# ConverterModule12V18A.net
KiCad netlist of a schematic drawn in Altium Designer
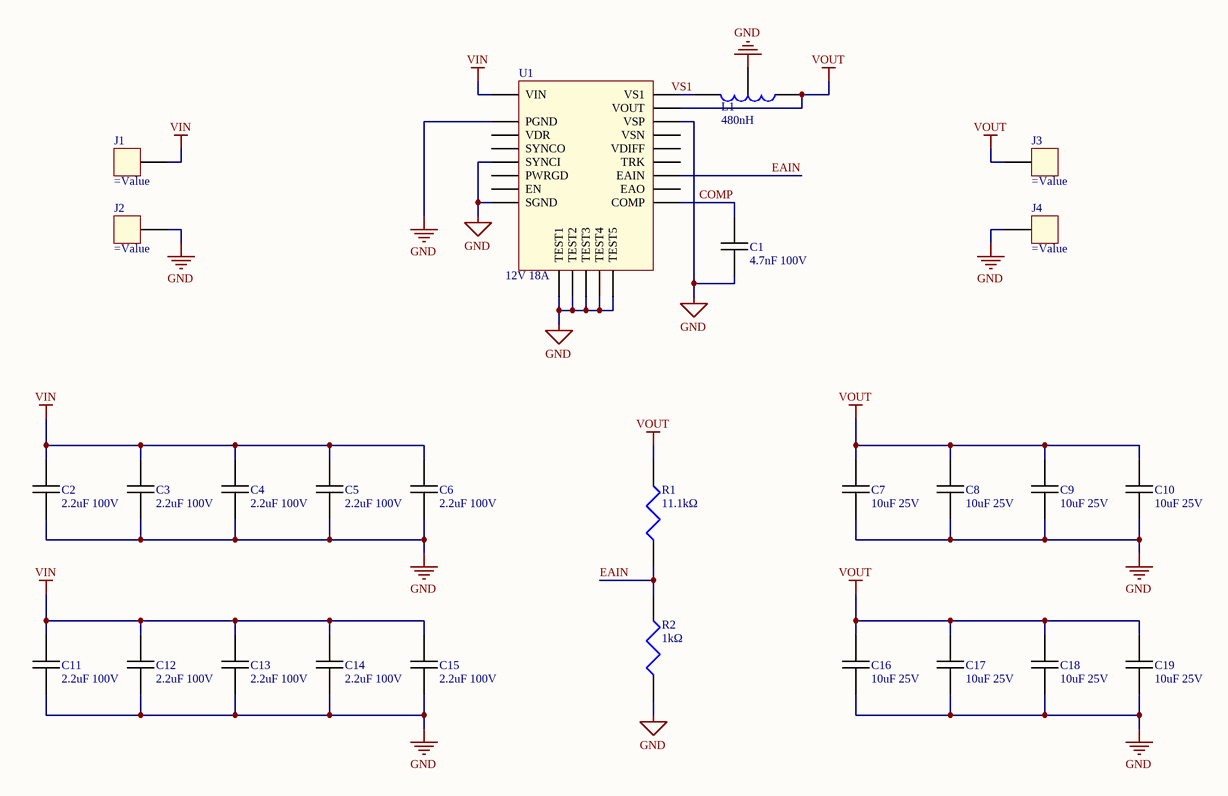
[diagram p0: ConverterModule12V18A.SchDoc]

(export (version "E")
  (design (tool "Eeschema 10.0.6"))
  (components
    (comp (ref "C1")
      (value "4.7nF 100V")
      (footprint "C1608 Generic")
      (description "TDK CAP CER 4700PF 100V C0G 0603")
      (fields
        (field (name "PART NUMBER") "C1608C0G2A472J080AC")
        (field (name "MANUFACTURER") "TDK Corporation")
      )
      (libsource (lib "MinesROV") (part "C1608C0G2A472J080AC"))
    )
    (comp (ref "C2")
      (value "2.2uF 100V")
      (footprint "HMK325B7225MM-P")
      (description "Taiyo Yuden CAP CER 2.2UF 100V X7R 1210")
      (fields (field (name "PART NUMBER") "HMK325B7225MM-P") (field (name "MANUFACTURER") "Taiyo Yuden"))
      (libsource (lib "MinesROV") (part "HMK325B7225MM-P"))
    )
    (comp (ref "C3")
      (value "2.2uF 100V")
      (footprint "HMK325B7225MM-P")
      (description "Taiyo Yuden CAP CER 2.2UF 100V X7R 1210")
      (fields (field (name "PART NUMBER") "HMK325B7225MM-P") (field (name "MANUFACTURER") "Taiyo Yuden"))
      (libsource (lib "MinesROV") (part "HMK325B7225MM-P"))
    )
    (comp (ref "C4")
      (value "2.2uF 100V")
      (footprint "HMK325B7225MM-P")
      (description "Taiyo Yuden CAP CER 2.2UF 100V X7R 1210")
      (fields (field (name "PART NUMBER") "HMK325B7225MM-P") (field (name "MANUFACTURER") "Taiyo Yuden"))
      (libsource (lib "MinesROV") (part "HMK325B7225MM-P"))
    )
    (comp (ref "C5")
      (value "2.2uF 100V")
      (footprint "HMK325B7225MM-P")
      (description "Taiyo Yuden CAP CER 2.2UF 100V X7R 1210")
      (fields (field (name "PART NUMBER") "HMK325B7225MM-P") (field (name "MANUFACTURER") "Taiyo Yuden"))
      (libsource (lib "MinesROV") (part "HMK325B7225MM-P"))
    )
    (comp (ref "C6")
      (value "2.2uF 100V")
      (footprint "HMK325B7225MM-P")
      (description "Taiyo Yuden CAP CER 2.2UF 100V X7R 1210")
      (fields (field (name "PART NUMBER") "HMK325B7225MM-P") (field (name "MANUFACTURER") "Taiyo Yuden"))
      (libsource (lib "MinesROV") (part "HMK325B7225MM-P"))
    )
    (comp (ref "C7")
      (value "10uF 25V")
      (footprint "C1210C106M3RACTU")
      (description "KEMET CAP CER 10UF 25V X7R 1210")
      (fields (field (name "PART NUMBER") "C1210C106M3RACTU") (field (name "MANUFACTURER") "KEMET"))
      (libsource (lib "MinesROV") (part "C1210C106M3RACTU"))
    )
    (comp (ref "C8")
      (value "10uF 25V")
      (footprint "C1210C106M3RACTU")
      (description "KEMET CAP CER 10UF 25V X7R 1210")
      (fields (field (name "PART NUMBER") "C1210C106M3RACTU") (field (name "MANUFACTURER") "KEMET"))
      (libsource (lib "MinesROV") (part "C1210C106M3RACTU"))
    )
    (comp (ref "C9")
      (value "10uF 25V")
      (footprint "C1210C106M3RACTU")
      (description "KEMET CAP CER 10UF 25V X7R 1210")
      (fields (field (name "PART NUMBER") "C1210C106M3RACTU") (field (name "MANUFACTURER") "KEMET"))
      (libsource (lib "MinesROV") (part "C1210C106M3RACTU"))
    )
    (comp (ref "C10")
      (value "10uF 25V")
      (footprint "C1210C106M3RACTU")
      (description "KEMET CAP CER 10UF 25V X7R 1210")
      (fields (field (name "PART NUMBER") "C1210C106M3RACTU") (field (name "MANUFACTURER") "KEMET"))
      (libsource (lib "MinesROV") (part "C1210C106M3RACTU"))
    )
    (comp (ref "C11")
      (value "2.2uF 100V")
      (footprint "HMK325B7225MM-P")
      (description "Taiyo Yuden CAP CER 2.2UF 100V X7R 1210")
      (fields (field (name "PART NUMBER") "HMK325B7225MM-P") (field (name "MANUFACTURER") "Taiyo Yuden"))
      (libsource (lib "MinesROV") (part "HMK325B7225MM-P"))
    )
    (comp (ref "C12")
      (value "2.2uF 100V")
      (footprint "HMK325B7225MM-P")
      (description "Taiyo Yuden CAP CER 2.2UF 100V X7R 1210")
      (fields (field (name "PART NUMBER") "HMK325B7225MM-P") (field (name "MANUFACTURER") "Taiyo Yuden"))
      (libsource (lib "MinesROV") (part "HMK325B7225MM-P"))
    )
    (comp (ref "C13")
      (value "2.2uF 100V")
      (footprint "HMK325B7225MM-P")
      (description "Taiyo Yuden CAP CER 2.2UF 100V X7R 1210")
      (fields (field (name "PART NUMBER") "HMK325B7225MM-P") (field (name "MANUFACTURER") "Taiyo Yuden"))
      (libsource (lib "MinesROV") (part "HMK325B7225MM-P"))
    )
    (comp (ref "C14")
      (value "2.2uF 100V")
      (footprint "HMK325B7225MM-P")
      (description "Taiyo Yuden CAP CER 2.2UF 100V X7R 1210")
      (fields (field (name "PART NUMBER") "HMK325B7225MM-P") (field (name "MANUFACTURER") "Taiyo Yuden"))
      (libsource (lib "MinesROV") (part "HMK325B7225MM-P"))
    )
    (comp (ref "C15")
      (value "2.2uF 100V")
      (footprint "HMK325B7225MM-P")
      (description "Taiyo Yuden CAP CER 2.2UF 100V X7R 1210")
      (fields (field (name "PART NUMBER") "HMK325B7225MM-P") (field (name "MANUFACTURER") "Taiyo Yuden"))
      (libsource (lib "MinesROV") (part "HMK325B7225MM-P"))
    )
    (comp (ref "C16")
      (value "10uF 25V")
      (footprint "C1210C106M3RACTU")
      (description "KEMET CAP CER 10UF 25V X7R 1210")
      (fields (field (name "PART NUMBER") "C1210C106M3RACTU") (field (name "MANUFACTURER") "KEMET"))
      (libsource (lib "MinesROV") (part "C1210C106M3RACTU"))
    )
    (comp (ref "C17")
      (value "10uF 25V")
      (footprint "C1210C106M3RACTU")
      (description "KEMET CAP CER 10UF 25V X7R 1210")
      (fields (field (name "PART NUMBER") "C1210C106M3RACTU") (field (name "MANUFACTURER") "KEMET"))
      (libsource (lib "MinesROV") (part "C1210C106M3RACTU"))
    )
    (comp (ref "C18")
      (value "10uF 25V")
      (footprint "C1210C106M3RACTU")
      (description "KEMET CAP CER 10UF 25V X7R 1210")
      (fields (field (name "PART NUMBER") "C1210C106M3RACTU") (field (name "MANUFACTURER") "KEMET"))
      (libsource (lib "MinesROV") (part "C1210C106M3RACTU"))
    )
    (comp (ref "C19")
      (value "10uF 25V")
      (footprint "C1210C106M3RACTU")
      (description "KEMET CAP CER 10UF 25V X7R 1210")
      (fields (field (name "PART NUMBER") "C1210C106M3RACTU") (field (name "MANUFACTURER") "KEMET"))
      (libsource (lib "MinesROV") (part "C1210C106M3RACTU"))
    )
    (comp (ref "J1")
      (value "~")
      (footprint "M3-Bolt-Down")
      (description "Generic bolt-down mount w/exposed copper pad")
      (libsource (lib "") (part "M3-Bolt-Down_1"))
    )
    (comp (ref "J2")
      (value "~")
      (footprint "M3-Bolt-Down")
      (description "Generic bolt-down mount w/exposed copper pad")
      (libsource (lib "") (part "M3-Bolt-Down_1"))
    )
    (comp (ref "J3")
      (value "~")
      (footprint "M3-Bolt-Down")
      (description "Generic bolt-down mount w/exposed copper pad")
      (libsource (lib "MinesROV") (part "M3-Bolt-Down"))
    )
    (comp (ref "J4")
      (value "~")
      (footprint "M3-Bolt-Down")
      (description "Generic bolt-down mount w/exposed copper pad")
      (libsource (lib "MinesROV") (part "M3-Bolt-Down"))
    )
    (comp (ref "L1")
      (value "480nH")
      (footprint "PA5120.481NLT")
      (description "Pulse FIXED IND 480NH 32A 1.7MOHM SMD")
      (fields
        (field (name "MANUFACTURER") "Pulse Electronics Power")
        (field (name "PART NUMBER") "PA5120.481NLT")
      )
      (libsource (lib "MinesROV") (part "PA5120.481NLT"))
    )
    (comp (ref "R1")
      (value "11.1kΩ")
      (footprint "RNCF0603 Generic")
      (description "Stackpole RES 11.1K OHM 0.1% 1/10W 0603")
      (fields
        (field (name "PART NUMBER") "RNCF0603BTE11K1")
        (field (name "MANUFACTURER") "Stackpole Electronics Inc")
      )
      (libsource (lib "MinesROV") (part "RNCF0603BTE11K1"))
    )
    (comp (ref "R2")
      (value "1kΩ")
      (footprint "RNCF0603 Generic")
      (description "Stackpole RES 1K OHM 0.01% 1/10W 0603")
      (fields
        (field (name "PART NUMBER") "RNCF0603TKY1K00")
        (field (name "MANUFACTURER") "Stackpole Electronics Inc")
      )
      (libsource (lib "MinesROV") (part "RNCF0603TKY1K00"))
    )
    (comp (ref "U1")
      (value "12V 18A")
      (footprint "PI3526-00-LGIZ")
      (description "Vicor DC DC CONVERTER 12V 18A")
      (fields (field (name "MANUFACTURER") "Vicor Corporation") (field (name "PART NUMBER") "PI3526-00-LGIZ"))
      (libsource (lib "MinesROV") (part "PI3526-00-LGIZ"))
    )
  )
  (nets
    (net (code "1") (name "/COMP") (class "Default")
      (node (ref "C1") (pin "1") (pinfunction "1_1") (pintype "passive"))
      (node (ref "U1") (pin "B1") (pinfunction "COMP_B1") (pintype "passive"))
    )
    (net (code "2") (name "/EAIN") (class "Default")
      (node (ref "R1") (pin "2") (pinfunction "2_2") (pintype "passive"))
      (node (ref "R2") (pin "2") (pinfunction "2_2") (pintype "passive"))
      (node (ref "U1") (pin "A2") (pinfunction "EAIN_A2") (pintype "passive"))
    )
    (net (code "3") (name "/VS1") (class "Default")
      (node (ref "L1") (pin "2") (pinfunction "2_2") (pintype "passive"))
      (node (ref "U1") (pin "BLOCK1") (pinfunction "VS1_BLOCK1") (pintype "passive"))
    )
    (net (code "4") (name "GND") (class "Default")
      (node (ref "C1") (pin "2") (pinfunction "2_2") (pintype "passive"))
      (node (ref "C10") (pin "1") (pinfunction "1_1") (pintype "passive"))
      (node (ref "C11") (pin "2") (pinfunction "2_2") (pintype "passive"))
      (node (ref "C12") (pin "2") (pinfunction "2_2") (pintype "passive"))
      (node (ref "C13") (pin "2") (pinfunction "2_2") (pintype "passive"))
      (node (ref "C14") (pin "2") (pinfunction "2_2") (pintype "passive"))
      (node (ref "C15") (pin "2") (pinfunction "2_2") (pintype "passive"))
      (node (ref "C16") (pin "1") (pinfunction "1_1") (pintype "passive"))
      (node (ref "C17") (pin "1") (pinfunction "1_1") (pintype "passive"))
      (node (ref "C18") (pin "1") (pinfunction "1_1") (pintype "passive"))
      (node (ref "C19") (pin "1") (pinfunction "1_1") (pintype "passive"))
      (node (ref "C2") (pin "2") (pinfunction "2_2") (pintype "passive"))
      (node (ref "C3") (pin "2") (pinfunction "2_2") (pintype "passive"))
      (node (ref "C4") (pin "2") (pinfunction "2_2") (pintype "passive"))
      (node (ref "C5") (pin "2") (pinfunction "2_2") (pintype "passive"))
      (node (ref "C6") (pin "2") (pinfunction "2_2") (pintype "passive"))
      (node (ref "C7") (pin "1") (pinfunction "1_1") (pintype "passive"))
      (node (ref "C8") (pin "1") (pinfunction "1_1") (pintype "passive"))
      (node (ref "C9") (pin "1") (pinfunction "1_1") (pintype "passive"))
      (node (ref "J2") (pin "1") (pinfunction "1_1") (pintype "passive"))
      (node (ref "J4") (pin "1") (pinfunction "1_1") (pintype "passive"))
      (node (ref "L1") (pin "3") (pinfunction "3_3") (pintype "passive"))
      (node (ref "R2") (pin "1") (pinfunction "1_1") (pintype "passive"))
      (node (ref "U1") (pin "A5") (pinfunction "VSP_A5") (pintype "passive"))
      (node (ref "U1") (pin "BLOCK2") (pinfunction "PGND_BLOCK2") (pintype "passive"))
      (node (ref "U1") (pin "BLOCK5") (pinfunction "SGND_BLOCK5") (pintype "passive"))
      (node (ref "U1") (pin "E1") (pinfunction "TEST5_E1") (pintype "passive"))
      (node (ref "U1") (pin "H1") (pinfunction "TEST4_H1") (pintype "passive"))
      (node (ref "U1") (pin "J1") (pinfunction "TEST3_J1") (pintype "passive"))
      (node (ref "U1") (pin "K1") (pinfunction "TEST2_K1") (pintype "passive"))
      (node (ref "U1") (pin "K2") (pinfunction "TEST1_K2") (pintype "passive"))
      (node (ref "U1") (pin "K4") (pinfunction "SYNCI_K4") (pintype "passive"))
    )
    (net (code "5") (name "VIN") (class "Default")
      (node (ref "C11") (pin "1") (pinfunction "1_1") (pintype "passive"))
      (node (ref "C12") (pin "1") (pinfunction "1_1") (pintype "passive"))
      (node (ref "C13") (pin "1") (pinfunction "1_1") (pintype "passive"))
      (node (ref "C14") (pin "1") (pinfunction "1_1") (pintype "passive"))
      (node (ref "C15") (pin "1") (pinfunction "1_1") (pintype "passive"))
      (node (ref "C2") (pin "1") (pinfunction "1_1") (pintype "passive"))
      (node (ref "C3") (pin "1") (pinfunction "1_1") (pintype "passive"))
      (node (ref "C4") (pin "1") (pinfunction "1_1") (pintype "passive"))
      (node (ref "C5") (pin "1") (pinfunction "1_1") (pintype "passive"))
      (node (ref "C6") (pin "1") (pinfunction "1_1") (pintype "passive"))
      (node (ref "J1") (pin "1") (pinfunction "1_1") (pintype "passive"))
      (node (ref "U1") (pin "BLOCK3") (pinfunction "VIN_BLOCK3") (pintype "passive"))
    )
    (net (code "6") (name "VOUT") (class "Default")
      (node (ref "C10") (pin "2") (pinfunction "2_2") (pintype "passive"))
      (node (ref "C16") (pin "2") (pinfunction "2_2") (pintype "passive"))
      (node (ref "C17") (pin "2") (pinfunction "2_2") (pintype "passive"))
      (node (ref "C18") (pin "2") (pinfunction "2_2") (pintype "passive"))
      (node (ref "C19") (pin "2") (pinfunction "2_2") (pintype "passive"))
      (node (ref "C7") (pin "2") (pinfunction "2_2") (pintype "passive"))
      (node (ref "C8") (pin "2") (pinfunction "2_2") (pintype "passive"))
      (node (ref "C9") (pin "2") (pinfunction "2_2") (pintype "passive"))
      (node (ref "J3") (pin "1") (pinfunction "1_1") (pintype "passive"))
      (node (ref "L1") (pin "1") (pinfunction "1_1") (pintype "passive"))
      (node (ref "R1") (pin "1") (pinfunction "1_1") (pintype "passive"))
      (node (ref "U1") (pin "BLOCK4") (pinfunction "VOUT_BLOCK4") (pintype "passive"))
    )
    (net (code "7") (name "unconnected-(U1-EAO-PadA1)") (class "Default")
      (node (ref "U1") (pin "A1") (pinfunction "EAO_A1") (pintype "passive"))
    )
    (net (code "8") (name "unconnected-(U1-EN-PadF1)") (class "Default")
      (node (ref "U1") (pin "F1") (pinfunction "EN_F1") (pintype "passive"))
    )
    (net (code "9") (name "unconnected-(U1-PWRGD-PadG1)") (class "Default")
      (node (ref "U1") (pin "G1") (pinfunction "PWRGD_G1") (pintype "passive"))
    )
    (net (code "10") (name "unconnected-(U1-SYNCO-PadK3)") (class "Default")
      (node (ref "U1") (pin "K3") (pinfunction "SYNCO_K3") (pintype "passive"))
    )
    (net (code "11") (name "unconnected-(U1-TRK-PadC1)") (class "Default")
      (node (ref "U1") (pin "C1") (pinfunction "TRK_C1") (pintype "passive"))
    )
    (net (code "12") (name "unconnected-(U1-VDIFF-PadA3)") (class "Default")
      (node (ref "U1") (pin "A3") (pinfunction "VDIFF_A3") (pintype "passive"))
    )
    (net (code "13") (name "unconnected-(U1-VDR-PadK5)") (class "Default")
      (node (ref "U1") (pin "K5") (pinfunction "VDR_K5") (pintype "passive"))
    )
    (net (code "14") (name "unconnected-(U1-VSN-PadA4)") (class "Default")
      (node (ref "U1") (pin "A4") (pinfunction "VSN_A4") (pintype "passive"))
    )
  )
)
